# QCopterRC_CAMSPI_Sch.net
KiCad netlist of a schematic drawn in Altium Designer
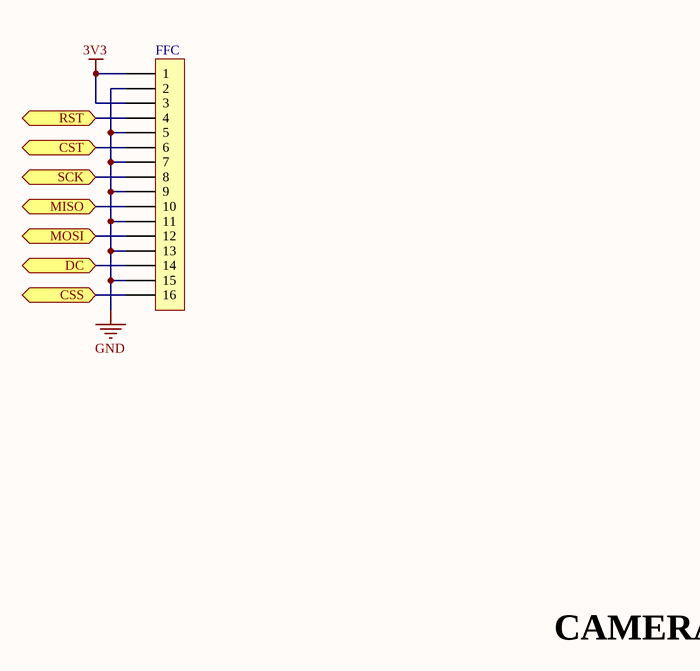
[diagram p0: QCopterRC_CAMSPI_Sch.SchDoc]

(export (version "E")
  (design (tool "Eeschema 10.0.6"))
  (components
    (comp (ref "FFC")
      (value "FFC_0.5_16")
      (footprint "PCB_Connector:FFC_0.5_16")
      (description "FFC")
      (libsource (lib "SCH_Connector") (part "FFC_0.5_16"))
    )
  )
  (nets
    (net (code "1") (name "/CSS") (class "Default")
      (node (ref "FFC") (pin "16") (pinfunction "16_16") (pintype "passive"))
    )
    (net (code "2") (name "/CST") (class "Default")
      (node (ref "FFC") (pin "6") (pinfunction "6_6") (pintype "passive"))
    )
    (net (code "3") (name "/DC") (class "Default")
      (node (ref "FFC") (pin "14") (pinfunction "14_14") (pintype "passive"))
    )
    (net (code "4") (name "/MISO") (class "Default")
      (node (ref "FFC") (pin "10") (pinfunction "10_10") (pintype "passive"))
    )
    (net (code "5") (name "/MOSI") (class "Default")
      (node (ref "FFC") (pin "12") (pinfunction "12_12") (pintype "passive"))
    )
    (net (code "6") (name "/RST") (class "Default")
      (node (ref "FFC") (pin "4") (pinfunction "4_4") (pintype "passive"))
    )
    (net (code "7") (name "/SCK") (class "Default")
      (node (ref "FFC") (pin "8") (pinfunction "8_8") (pintype "passive"))
    )
    (net (code "8") (name "3V3") (class "Default")
      (node (ref "FFC") (pin "1") (pinfunction "1_1") (pintype "passive"))
      (node (ref "FFC") (pin "3") (pinfunction "3_3") (pintype "passive"))
    )
    (net (code "9") (name "GND") (class "Default")
      (node (ref "FFC") (pin "11") (pinfunction "11_11") (pintype "passive"))
      (node (ref "FFC") (pin "13") (pinfunction "13_13") (pintype "passive"))
      (node (ref "FFC") (pin "15") (pinfunction "15_15") (pintype "passive"))
      (node (ref "FFC") (pin "2") (pinfunction "2_2") (pintype "passive"))
      (node (ref "FFC") (pin "5") (pinfunction "5_5") (pintype "passive"))
      (node (ref "FFC") (pin "7") (pinfunction "7_7") (pintype "passive"))
      (node (ref "FFC") (pin "9") (pinfunction "9_9") (pintype "passive"))
    )
  )
)
